# single-apa102c.net
KiCad netlist of a schematic drawn in EAGLE
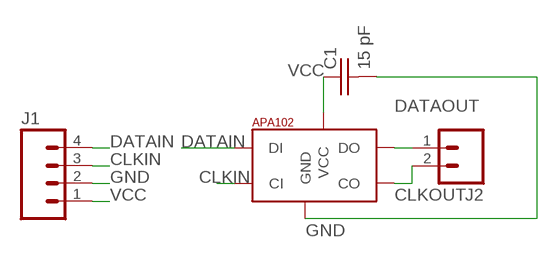
[diagram p0: schematic, sheet 1]
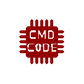
[diagram p1: schematic, sheet 2]

(export (version "E")
  (design (tool "Eeschema 10.0.6"))
  (components
    (comp (ref "U$2")
      (value "CMD_C0DE_LOGOCMD_CODE_LOGO_TOP_COPPER")
      (footprint "eagle-import:CMD_C0DE_LOGO_TOP_COPPER")
      (libsource (lib "eagle-import") (part "CMD_C0DE_LOGOCMD_CODE_LOGO_TOP_COPPER"))
    )
    (comp (ref "C1")
      (value "15 pF")
      (footprint "eagle-import:C0805K")
      (libsource (lib "eagle-import") (part "C-USC0805K"))
    )
    (comp (ref "J1")
      (value "M04PTH")
      (footprint "eagle-import:1X04")
      (libsource (lib "eagle-import") (part "M04PTH"))
    )
    (comp (ref "J2")
      (value "M02PTH")
      (footprint "eagle-import:1X02")
      (libsource (lib "eagle-import") (part "M02PTH"))
    )
    (comp (ref "U$1")
      (value "APA1025050")
      (footprint "eagle-import:APA102_5050")
      (libsource (lib "eagle-import") (part "APA1025050"))
    )
  )
  (nets
    (net (code "1") (name "CLKIN") (class "Default")
      (node (ref "J1") (pin "3") (pinfunction "3_3") (pintype "passive"))
      (node (ref "U$1") (pin "5") (pinfunction "CI_5") (pintype "bidirectional"))
    )
    (net (code "2") (name "CLKOUT") (class "Default")
      (node (ref "J2") (pin "2") (pinfunction "2_2") (pintype "passive"))
      (node (ref "U$1") (pin "2") (pinfunction "CO_2") (pintype "bidirectional"))
    )
    (net (code "3") (name "DATAIN") (class "Default")
      (node (ref "J1") (pin "4") (pinfunction "4_4") (pintype "passive"))
      (node (ref "U$1") (pin "4") (pinfunction "DI_4") (pintype "bidirectional"))
    )
    (net (code "4") (name "DATAOUT") (class "Default")
      (node (ref "J2") (pin "1") (pinfunction "1_1") (pintype "passive"))
      (node (ref "U$1") (pin "3") (pinfunction "DO_3") (pintype "bidirectional"))
    )
    (net (code "5") (name "GND") (class "Default")
      (node (ref "C1") (pin "2") (pinfunction "2_2") (pintype "passive"))
      (node (ref "J1") (pin "2") (pinfunction "2_2") (pintype "passive"))
      (node (ref "U$1") (pin "6") (pinfunction "GND_6") (pintype "bidirectional"))
    )
    (net (code "6") (name "VCC") (class "Default")
      (node (ref "C1") (pin "1") (pinfunction "1_1") (pintype "passive"))
      (node (ref "J1") (pin "1") (pinfunction "1_1") (pintype "passive"))
      (node (ref "U$1") (pin "1") (pinfunction "VCC_1") (pintype "bidirectional"))
    )
  )
)
